# RF1_RS485.net
KiCad netlist of a schematic drawn in EAGLE
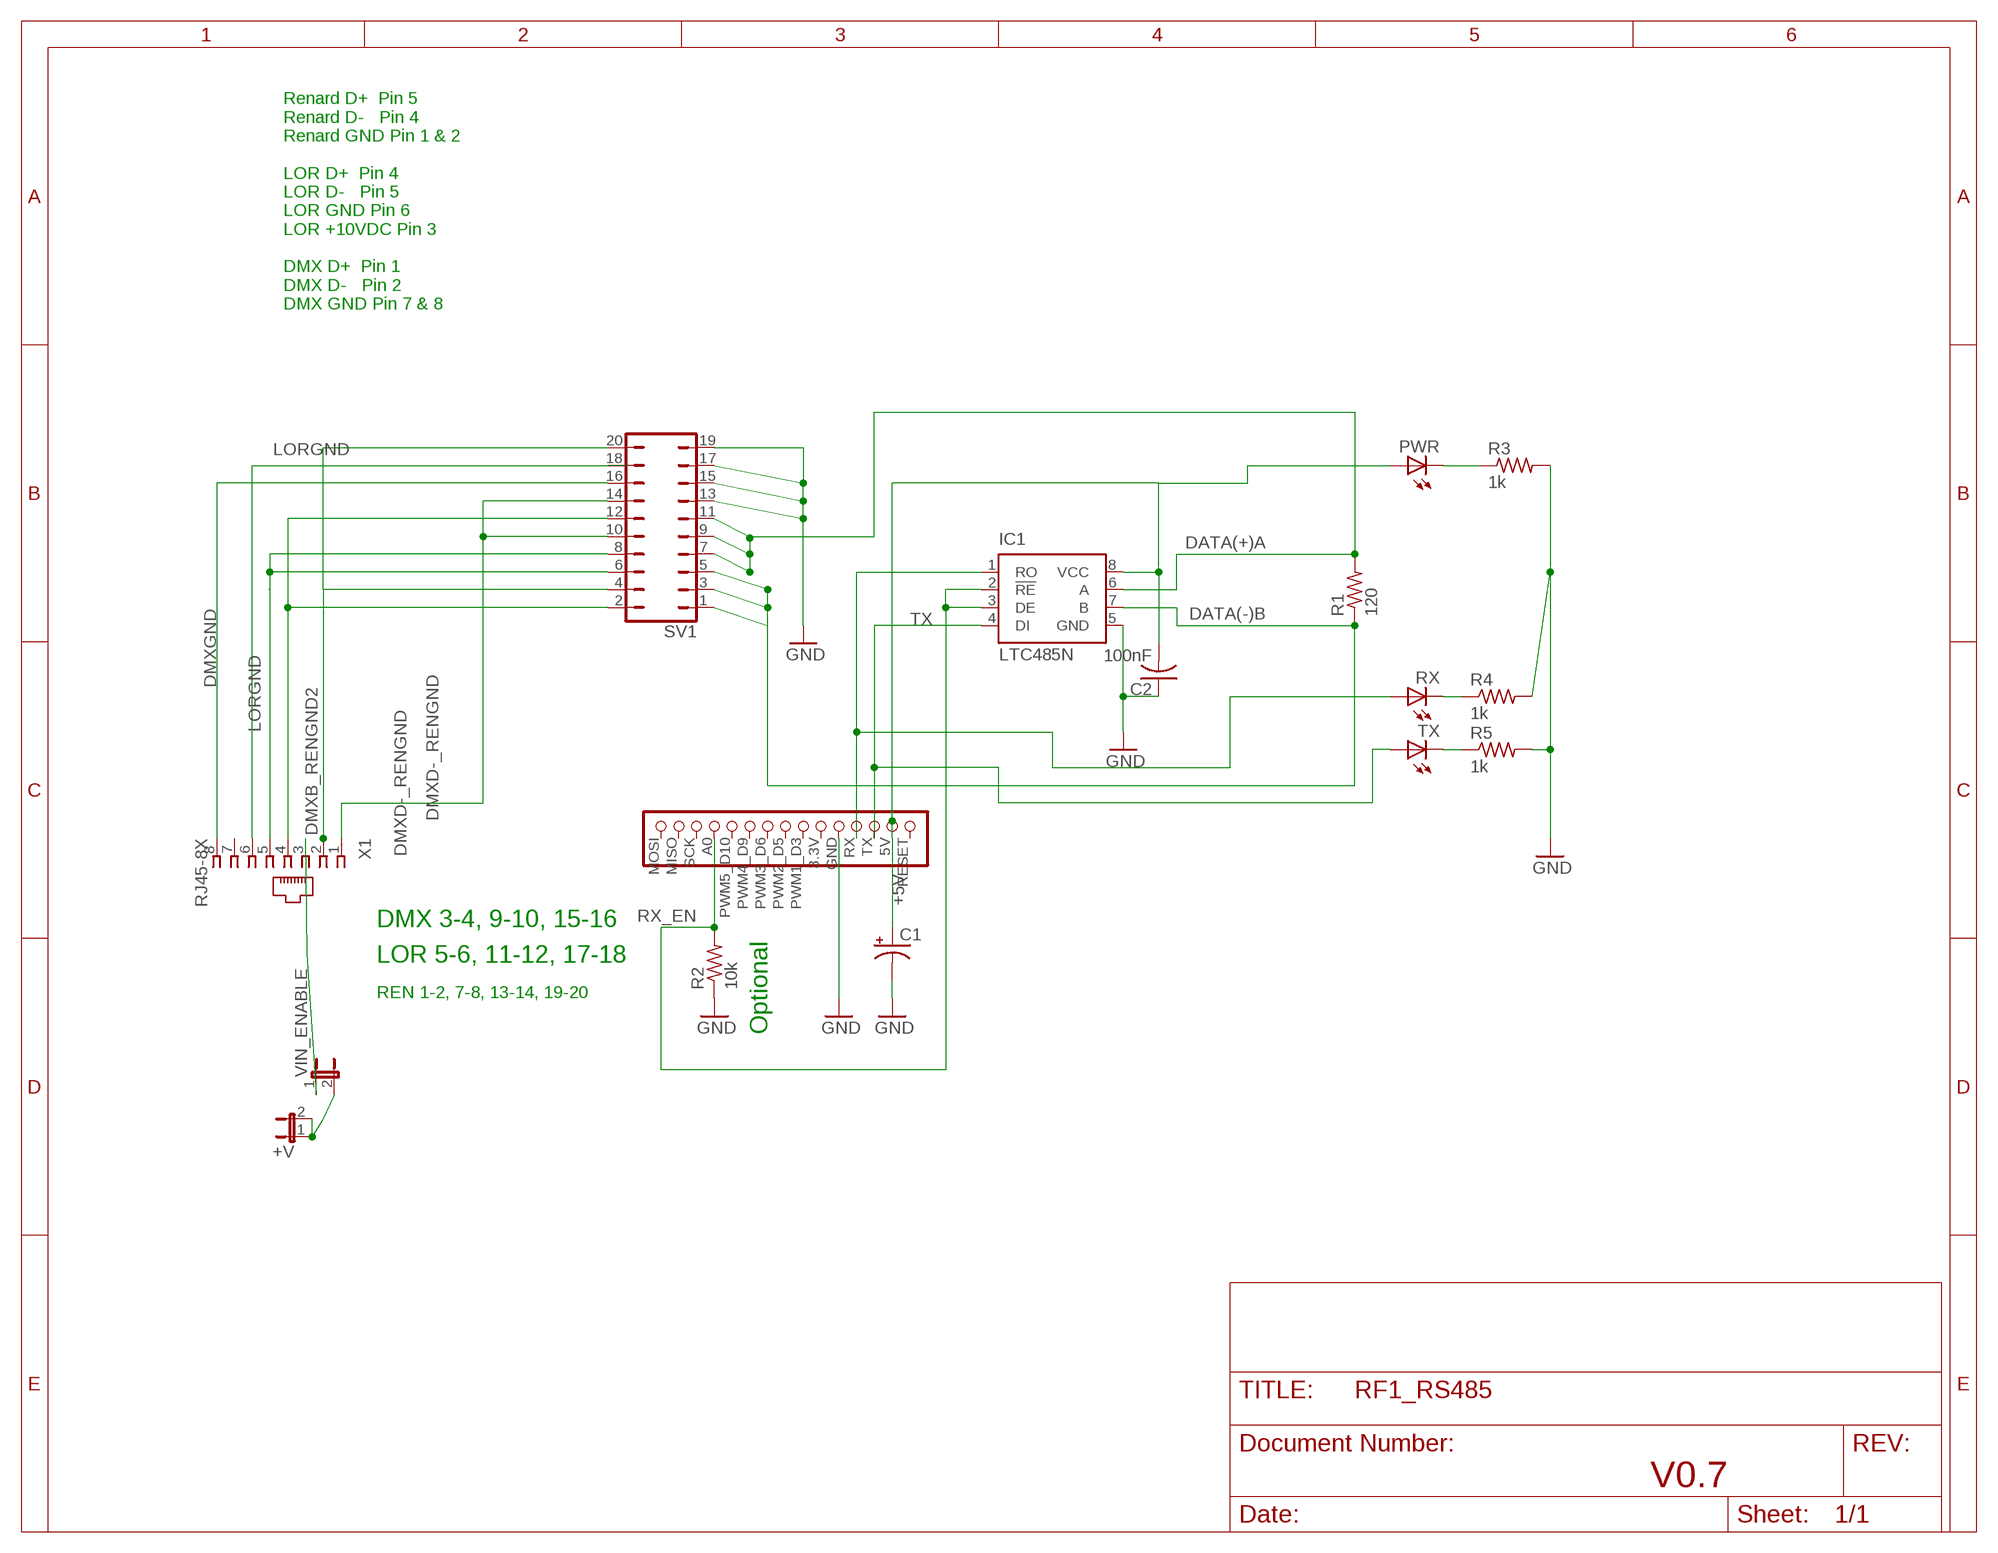
[diagram p0: schematic, sheet 1]

(export (version "E")
  (design (tool "Eeschema 10.0.6"))
  (components
    (comp (ref "+V")
      (value "JP1E")
      (footprint "eagle-import:JP1")
      (libsource (lib "eagle-import") (part "JP1E"))
    )
    (comp (ref "C1")
      (value "CPOL-USE5-5")
      (footprint "eagle-import:E5-5")
      (libsource (lib "eagle-import") (part "CPOL-USE5-5"))
    )
    (comp (ref "C2")
      (value "100nF")
      (footprint "eagle-import:C025-024X044")
      (libsource (lib "eagle-import") (part "C-US025-024X044"))
    )
    (comp (ref "IC1")
      (value "LTC485N")
      (footprint "eagle-import:DIL08")
      (libsource (lib "eagle-import") (part "LTC485N"))
    )
    (comp (ref "PWR")
      (value "LED3MM")
      (footprint "eagle-import:LED3MM")
      (libsource (lib "eagle-import") (part "LED3MM"))
    )
    (comp (ref "R1")
      (value "120")
      (footprint "eagle-import:0204_7")
      (libsource (lib "eagle-import") (part "R-US_0204/7"))
    )
    (comp (ref "R2")
      (value "10k")
      (footprint "eagle-import:0204_7")
      (libsource (lib "eagle-import") (part "R-US_0204/7"))
    )
    (comp (ref "R3")
      (value "1k")
      (footprint "eagle-import:0204_7")
      (libsource (lib "eagle-import") (part "R-US_0204/7"))
    )
    (comp (ref "R4")
      (value "1k")
      (footprint "eagle-import:0204_7")
      (libsource (lib "eagle-import") (part "R-US_0204/7"))
    )
    (comp (ref "R5")
      (value "1k")
      (footprint "eagle-import:0204_7")
      (libsource (lib "eagle-import") (part "R-US_0204/7"))
    )
    (comp (ref "RX")
      (value "LED3MM")
      (footprint "eagle-import:LED3MM")
      (libsource (lib "eagle-import") (part "LED3MM"))
    )
    (comp (ref "SV1")
      (value "JP10Q")
      (footprint "eagle-import:JP10Q")
      (libsource (lib "eagle-import") (part "JP10Q"))
    )
    (comp (ref "TX")
      (value "LED3MM")
      (footprint "eagle-import:LED3MM")
      (libsource (lib "eagle-import") (part "LED3MM"))
    )
    (comp (ref "U$1")
      (value "RF1_HEADER_LEFT")
      (footprint "eagle-import:RF1_LEFTHEADER_ONLY")
      (libsource (lib "eagle-import") (part "RF1_HEADER_LEFT"))
    )
    (comp (ref "VIN_ENABLE")
      (value "JP1E")
      (footprint "eagle-import:JP1")
      (libsource (lib "eagle-import") (part "JP1E"))
    )
    (comp (ref "X1")
      (value "RJ45-8X")
      (footprint "eagle-import:RJ45-NO-SHIELD")
      (libsource (lib "eagle-import") (part "RJ45-8X"))
    )
  )
  (nets
    (net (code "1") (name "/+5V") (class "Default")
      (node (ref "C1") (pin "+") (pinfunction "+_+") (pintype "passive"))
      (node (ref "C2") (pin "2") (pinfunction "2_2") (pintype "passive"))
      (node (ref "IC1") (pin "8") (pinfunction "VCC_8") (pintype "input"))
      (node (ref "PWR") (pin "A") (pinfunction "A_A") (pintype "passive"))
      (node (ref "U$1") (pin "5V") (pinfunction "5V_5V") (pintype "passive"))
    )
    (net (code "2") (name "/DATA(+)A") (class "Default")
      (node (ref "IC1") (pin "6") (pinfunction "A_6") (pintype "bidirectional"))
      (node (ref "R1") (pin "2") (pinfunction "2_2") (pintype "passive"))
      (node (ref "SV1") (pin "11") (pinfunction "11_11") (pintype "passive"))
      (node (ref "SV1") (pin "7") (pinfunction "7_7") (pintype "passive"))
      (node (ref "SV1") (pin "9") (pinfunction "9_9") (pintype "passive"))
    )
    (net (code "3") (name "/DATA(-)B") (class "Default")
      (node (ref "IC1") (pin "7") (pinfunction "B_7") (pintype "bidirectional"))
      (node (ref "R1") (pin "1") (pinfunction "1_1") (pintype "passive"))
      (node (ref "SV1") (pin "1") (pinfunction "1_1") (pintype "passive"))
      (node (ref "SV1") (pin "3") (pinfunction "3_3") (pintype "passive"))
      (node (ref "SV1") (pin "5") (pinfunction "5_5") (pintype "passive"))
    )
    (net (code "4") (name "/DMXB_RENGND2") (class "Default")
      (node (ref "SV1") (pin "20") (pinfunction "20_20") (pintype "passive"))
      (node (ref "SV1") (pin "4") (pinfunction "4_4") (pintype "passive"))
      (node (ref "X1") (pin "2") (pinfunction "2_2") (pintype "passive"))
    )
    (net (code "5") (name "/DMXD-_RENGND") (class "Default")
      (node (ref "SV1") (pin "10") (pinfunction "10_10") (pintype "passive"))
      (node (ref "SV1") (pin "14") (pinfunction "14_14") (pintype "passive"))
      (node (ref "X1") (pin "1") (pinfunction "1_1") (pintype "passive"))
    )
    (net (code "6") (name "/DMXGND") (class "Default")
      (node (ref "SV1") (pin "16") (pinfunction "16_16") (pintype "passive"))
      (node (ref "X1") (pin "8") (pinfunction "8_8") (pintype "passive"))
    )
    (net (code "7") (name "/LORGND") (class "Default")
      (node (ref "SV1") (pin "18") (pinfunction "18_18") (pintype "passive"))
      (node (ref "X1") (pin "6") (pinfunction "6_6") (pintype "passive"))
    )
    (net (code "8") (name "/RX_EN") (class "Default")
      (node (ref "IC1") (pin "2") (pinfunction "~{RE}_2") (pintype "input"))
      (node (ref "IC1") (pin "3") (pinfunction "DE_3") (pintype "input"))
      (node (ref "R2") (pin "2") (pinfunction "2_2") (pintype "passive"))
      (node (ref "U$1") (pin "A0") (pinfunction "PC0_A0") (pintype "passive"))
    )
    (net (code "9") (name "/TX") (class "Default")
      (node (ref "IC1") (pin "4") (pinfunction "DI_4") (pintype "input"))
      (node (ref "TX") (pin "A") (pinfunction "A_A") (pintype "passive"))
      (node (ref "U$1") (pin "TX") (pinfunction "TX_TX") (pintype "passive"))
    )
    (net (code "10") (name "GND") (class "Default")
      (node (ref "C1") (pin "-") (pinfunction "-_-") (pintype "passive"))
      (node (ref "C2") (pin "1") (pinfunction "1_1") (pintype "passive"))
      (node (ref "IC1") (pin "5") (pinfunction "GND_5") (pintype "input"))
      (node (ref "R2") (pin "1") (pinfunction "1_1") (pintype "passive"))
      (node (ref "R3") (pin "2") (pinfunction "2_2") (pintype "passive"))
      (node (ref "R4") (pin "2") (pinfunction "2_2") (pintype "passive"))
      (node (ref "R5") (pin "2") (pinfunction "2_2") (pintype "passive"))
      (node (ref "SV1") (pin "13") (pinfunction "13_13") (pintype "passive"))
      (node (ref "SV1") (pin "15") (pinfunction "15_15") (pintype "passive"))
      (node (ref "SV1") (pin "17") (pinfunction "17_17") (pintype "passive"))
      (node (ref "SV1") (pin "19") (pinfunction "19_19") (pintype "passive"))
      (node (ref "U$1") (pin "GND") (pinfunction "GND_GND") (pintype "passive"))
    )
    (net (code "11") (name "Net-(+V-Pad1)") (class "Default")
      (node (ref "+V") (pin "1") (pinfunction "1_1") (pintype "passive"))
      (node (ref "+V") (pin "2") (pinfunction "2_2") (pintype "passive"))
      (node (ref "VIN_ENABLE") (pin "2") (pinfunction "2_2") (pintype "passive"))
    )
    (net (code "12") (name "Net-(IC1-RO)") (class "Default")
      (node (ref "IC1") (pin "1") (pinfunction "RO_1") (pintype "output"))
      (node (ref "RX") (pin "A") (pinfunction "A_A") (pintype "passive"))
      (node (ref "U$1") (pin "RX") (pinfunction "RX_RX") (pintype "passive"))
    )
    (net (code "13") (name "Net-(PWR-C)") (class "Default")
      (node (ref "PWR") (pin "K") (pinfunction "C_K") (pintype "passive"))
      (node (ref "R3") (pin "1") (pinfunction "1_1") (pintype "passive"))
    )
    (net (code "14") (name "Net-(RX-C)") (class "Default")
      (node (ref "R4") (pin "1") (pinfunction "1_1") (pintype "passive"))
      (node (ref "RX") (pin "K") (pinfunction "C_K") (pintype "passive"))
    )
    (net (code "15") (name "Net-(SV1-Pad6)") (class "Default")
      (node (ref "SV1") (pin "6") (pinfunction "6_6") (pintype "passive"))
      (node (ref "SV1") (pin "8") (pinfunction "8_8") (pintype "passive"))
      (node (ref "X1") (pin "5") (pinfunction "5_5") (pintype "passive"))
    )
    (net (code "16") (name "Net-(SV1-Pad12)") (class "Default")
      (node (ref "SV1") (pin "12") (pinfunction "12_12") (pintype "passive"))
      (node (ref "SV1") (pin "2") (pinfunction "2_2") (pintype "passive"))
      (node (ref "X1") (pin "4") (pinfunction "4_4") (pintype "passive"))
    )
    (net (code "17") (name "Net-(TX-C)") (class "Default")
      (node (ref "R5") (pin "1") (pinfunction "1_1") (pintype "passive"))
      (node (ref "TX") (pin "K") (pinfunction "C_K") (pintype "passive"))
    )
    (net (code "18") (name "Net-(VIN_ENABLE-Pad1)") (class "Default")
      (node (ref "VIN_ENABLE") (pin "1") (pinfunction "1_1") (pintype "passive"))
      (node (ref "X1") (pin "3") (pinfunction "3_3") (pintype "passive"))
    )
    (net (code "19") (name "unconnected-(U$1-PWM1-PadPWM1_D3)") (class "Default")
      (node (ref "U$1") (pin "PWM1_D3") (pinfunction "PWM1_PWM1_D3") (pintype "passive"))
    )
    (net (code "20") (name "unconnected-(U$1-PWM2-PadPWM2_D5)") (class "Default")
      (node (ref "U$1") (pin "PWM2_D5") (pinfunction "PWM2_PWM2_D5") (pintype "passive"))
    )
    (net (code "21") (name "unconnected-(U$1-PWM3-PadPWM3_D6)") (class "Default")
      (node (ref "U$1") (pin "PWM3_D6") (pinfunction "PWM3_PWM3_D6") (pintype "passive"))
    )
    (net (code "22") (name "unconnected-(U$1-PWM4-PadPWM4_D9)") (class "Default")
      (node (ref "U$1") (pin "PWM4_D9") (pinfunction "PWM4_PWM4_D9") (pintype "passive"))
    )
    (net (code "23") (name "unconnected-(U$1-PWM5-PadPWM5_D10)") (class "Default")
      (node (ref "U$1") (pin "PWM5_D10") (pinfunction "PWM5_PWM5_D10") (pintype "passive"))
    )
    (net (code "24") (name "unconnected-(U$1-Pad3.3V)") (class "Default")
      (node (ref "U$1") (pin "3.3V") (pinfunction "3.3V_3.3V") (pintype "passive"))
    )
    (net (code "25") (name "unconnected-(U$1-PadMISO)") (class "Default")
      (node (ref "U$1") (pin "MISO") (pinfunction "MISO_MISO") (pintype "passive"))
    )
    (net (code "26") (name "unconnected-(U$1-PadMOSI)") (class "Default")
      (node (ref "U$1") (pin "MOSI") (pinfunction "MOSI_MOSI") (pintype "passive"))
    )
    (net (code "27") (name "unconnected-(U$1-PadRESET)") (class "Default")
      (node (ref "U$1") (pin "RESET") (pinfunction "RESET_RESET") (pintype "passive"))
    )
    (net (code "28") (name "unconnected-(U$1-PadSCK)") (class "Default")
      (node (ref "U$1") (pin "SCK") (pinfunction "SCK_SCK") (pintype "passive"))
    )
    (net (code "29") (name "unconnected-(X1-Pad7)") (class "Default")
      (node (ref "X1") (pin "7") (pinfunction "7_7") (pintype "passive"))
    )
  )
)
